# candy_v0001.net
KiCad netlist of a schematic drawn in EAGLE
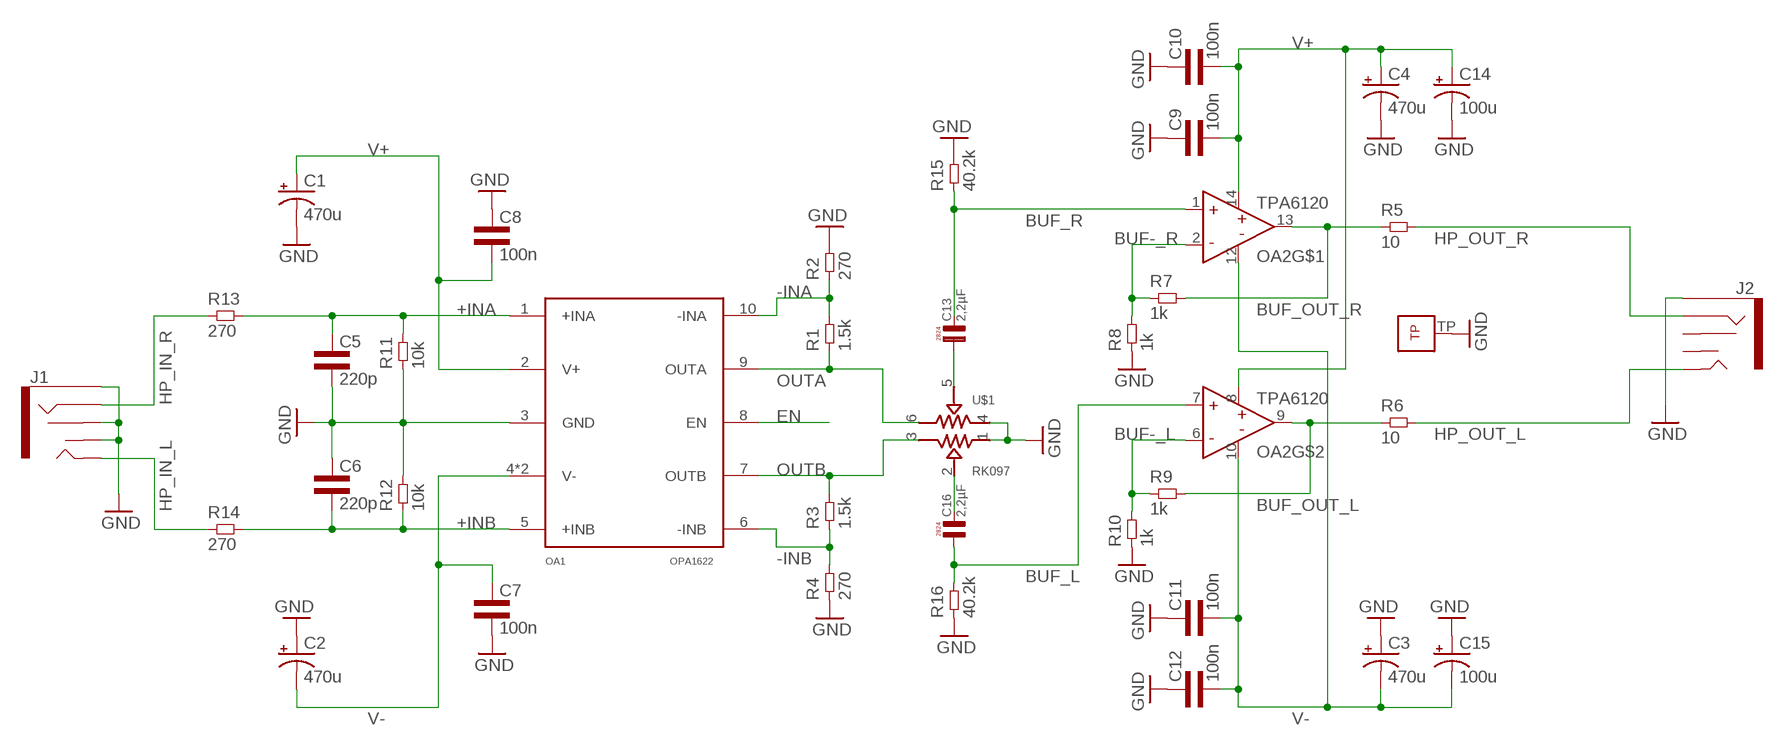
[diagram p0: schematic, sheet 1]

(export (version "E")
  (design (tool "Eeschema 10.0.6"))
  (components
    (comp (ref "C1")
      (value "470u")
      (footprint "eagle-import:PANASONIC_F")
      (libsource (lib "eagle-import") (part "CPOL-USF"))
    )
    (comp (ref "C2")
      (value "470u")
      (footprint "eagle-import:PANASONIC_F")
      (libsource (lib "eagle-import") (part "CPOL-USF"))
    )
    (comp (ref "C3")
      (value "470u")
      (footprint "eagle-import:PANASONIC_F")
      (libsource (lib "eagle-import") (part "CPOL-USF"))
    )
    (comp (ref "C4")
      (value "470u")
      (footprint "eagle-import:PANASONIC_F")
      (libsource (lib "eagle-import") (part "CPOL-USF"))
    )
    (comp (ref "C5")
      (value "220p")
      (footprint "eagle-import:0805L3")
      (libsource (lib "eagle-import") (part "CAP0805L3"))
    )
    (comp (ref "C6")
      (value "220p")
      (footprint "eagle-import:0805L3")
      (libsource (lib "eagle-import") (part "CAP0805L3"))
    )
    (comp (ref "C7")
      (value "100n")
      (footprint "eagle-import:0603L3")
      (libsource (lib "eagle-import") (part "CAP0603L3"))
    )
    (comp (ref "C8")
      (value "100n")
      (footprint "eagle-import:0603L3")
      (libsource (lib "eagle-import") (part "CAP0603L3"))
    )
    (comp (ref "C9")
      (value "100n")
      (footprint "eagle-import:0603L3")
      (libsource (lib "eagle-import") (part "CAP0603L3"))
    )
    (comp (ref "C10")
      (value "100n")
      (footprint "eagle-import:0603L3")
      (libsource (lib "eagle-import") (part "CAP0603L3"))
    )
    (comp (ref "C11")
      (value "100n")
      (footprint "eagle-import:0603L3")
      (libsource (lib "eagle-import") (part "CAP0603L3"))
    )
    (comp (ref "C12")
      (value "100n")
      (footprint "eagle-import:0603L3")
      (libsource (lib "eagle-import") (part "CAP0603L3"))
    )
    (comp (ref "C13")
      (value "2,2µF")
      (footprint "eagle-import:L7,2")
      (libsource (lib "eagle-import") (part "2,2µF"))
    )
    (comp (ref "C14")
      (value "100u")
      (footprint "eagle-import:PANASONIC_D")
      (libsource (lib "eagle-import") (part "CPOL-USD"))
    )
    (comp (ref "C15")
      (value "100u")
      (footprint "eagle-import:PANASONIC_D")
      (libsource (lib "eagle-import") (part "CPOL-USD"))
    )
    (comp (ref "C16")
      (value "2,2µF")
      (footprint "eagle-import:L7,2")
      (libsource (lib "eagle-import") (part "2,2µF"))
    )
    (comp (ref "J1")
      (value "AUDIO-JACK2SMD")
      (footprint "eagle-import:AUDIO-JACK-3.5MM-SMD")
      (libsource (lib "eagle-import") (part "AUDIO-JACK2SMD"))
    )
    (comp (ref "J2")
      (value "AUDIO-JACK2SMD")
      (footprint "eagle-import:AUDIO-JACK-3.5MM-SMD")
      (libsource (lib "eagle-import") (part "AUDIO-JACK2SMD"))
    )
    (comp (ref "OA1")
      (value "OPA1622")
      (footprint "eagle-import:S-PVSON-N10")
      (libsource (lib "eagle-import") (part "OPA1622"))
    )
    (comp (ref "OA2")
      (value "TPA6120QFN")
      (footprint "eagle-import:S-PVQFN-N14")
      (libsource (lib "eagle-import") (part "TPA6120QFN"))
    )
    (comp (ref "R1")
      (value "1.5k")
      (footprint "eagle-import:0603L3")
      (libsource (lib "eagle-import") (part "RES0603L3"))
    )
    (comp (ref "R2")
      (value "270")
      (footprint "eagle-import:0603L3")
      (libsource (lib "eagle-import") (part "RES0603L3"))
    )
    (comp (ref "R3")
      (value "1.5k")
      (footprint "eagle-import:0603L3")
      (libsource (lib "eagle-import") (part "RES0603L3"))
    )
    (comp (ref "R4")
      (value "270")
      (footprint "eagle-import:0603L3")
      (libsource (lib "eagle-import") (part "RES0603L3"))
    )
    (comp (ref "R5")
      (value "10")
      (footprint "eagle-import:1206L3")
      (libsource (lib "eagle-import") (part "RES1206L3"))
    )
    (comp (ref "R6")
      (value "10")
      (footprint "eagle-import:1206L3")
      (libsource (lib "eagle-import") (part "RES1206L3"))
    )
    (comp (ref "R7")
      (value "1k")
      (footprint "eagle-import:0603L3")
      (libsource (lib "eagle-import") (part "RES0603L3"))
    )
    (comp (ref "R8")
      (value "1k")
      (footprint "eagle-import:0603L3")
      (libsource (lib "eagle-import") (part "RES0603L3"))
    )
    (comp (ref "R9")
      (value "1k")
      (footprint "eagle-import:0603L3")
      (libsource (lib "eagle-import") (part "RES0603L3"))
    )
    (comp (ref "R10")
      (value "1k")
      (footprint "eagle-import:0603L3")
      (libsource (lib "eagle-import") (part "RES0603L3"))
    )
    (comp (ref "R11")
      (value "10k")
      (footprint "eagle-import:0603L3")
      (libsource (lib "eagle-import") (part "RES0603L3"))
    )
    (comp (ref "R12")
      (value "10k")
      (footprint "eagle-import:0603L3")
      (libsource (lib "eagle-import") (part "RES0603L3"))
    )
    (comp (ref "R13")
      (value "270")
      (footprint "eagle-import:0603L3")
      (libsource (lib "eagle-import") (part "RES0603L3"))
    )
    (comp (ref "R14")
      (value "270")
      (footprint "eagle-import:0603L3")
      (libsource (lib "eagle-import") (part "RES0603L3"))
    )
    (comp (ref "R15")
      (value "40.2k")
      (footprint "eagle-import:0603L3")
      (libsource (lib "eagle-import") (part "RES0603L3"))
    )
    (comp (ref "R16")
      (value "40.2k")
      (footprint "eagle-import:0603L3")
      (libsource (lib "eagle-import") (part "RES0603L3"))
    )
    (comp (ref "U$1")
      (value "RK097")
      (footprint "eagle-import:RK097")
      (libsource (lib "eagle-import") (part "RK097"))
    )
  )
  (nets
    (net (code "1") (name "/+INA") (class "Default")
      (node (ref "C5") (pin "1") (pinfunction "1_1") (pintype "bidirectional"))
      (node (ref "OA1") (pin "1") (pinfunction "+INA_1") (pintype "bidirectional"))
      (node (ref "R11") (pin "P$2") (pinfunction "2_P$2") (pintype "bidirectional"))
      (node (ref "R13") (pin "P$2") (pinfunction "2_P$2") (pintype "bidirectional"))
    )
    (net (code "2") (name "/+INB") (class "Default")
      (node (ref "C6") (pin "2") (pinfunction "2_2") (pintype "bidirectional"))
      (node (ref "OA1") (pin "5") (pinfunction "+INB_5") (pintype "bidirectional"))
      (node (ref "R12") (pin "P$1") (pinfunction "1_P$1") (pintype "bidirectional"))
      (node (ref "R14") (pin "P$2") (pinfunction "2_P$2") (pintype "bidirectional"))
    )
    (net (code "3") (name "/-INA") (class "Default")
      (node (ref "OA1") (pin "10") (pinfunction "-INA_10") (pintype "bidirectional"))
      (node (ref "R1") (pin "P$2") (pinfunction "2_P$2") (pintype "bidirectional"))
      (node (ref "R2") (pin "P$1") (pinfunction "1_P$1") (pintype "bidirectional"))
    )
    (net (code "4") (name "/-INB") (class "Default")
      (node (ref "OA1") (pin "6") (pinfunction "-INB_6") (pintype "bidirectional"))
      (node (ref "R3") (pin "P$1") (pinfunction "1_P$1") (pintype "bidirectional"))
      (node (ref "R4") (pin "P$2") (pinfunction "2_P$2") (pintype "bidirectional"))
    )
    (net (code "5") (name "/BUF-_L") (class "Default")
      (node (ref "OA2") (pin "6") (pinfunction "IN-_6") (pintype "bidirectional"))
      (node (ref "R10") (pin "P$2") (pinfunction "2_P$2") (pintype "bidirectional"))
      (node (ref "R9") (pin "P$1") (pinfunction "1_P$1") (pintype "bidirectional"))
    )
    (net (code "6") (name "/BUF-_R") (class "Default")
      (node (ref "OA2") (pin "2") (pinfunction "IN-_2") (pintype "bidirectional"))
      (node (ref "R7") (pin "P$1") (pinfunction "1_P$1") (pintype "bidirectional"))
      (node (ref "R8") (pin "P$2") (pinfunction "2_P$2") (pintype "bidirectional"))
    )
    (net (code "7") (name "/BUF_L") (class "Default")
      (node (ref "C16") (pin "P$1") (pinfunction "1_P$1") (pintype "passive"))
      (node (ref "OA2") (pin "7") (pinfunction "IN+_7") (pintype "bidirectional"))
      (node (ref "R16") (pin "P$2") (pinfunction "2_P$2") (pintype "bidirectional"))
    )
    (net (code "8") (name "/BUF_OUT_L") (class "Default")
      (node (ref "OA2") (pin "9") (pinfunction "OUT_9") (pintype "bidirectional"))
      (node (ref "R6") (pin "1") (pinfunction "1_1") (pintype "bidirectional"))
      (node (ref "R9") (pin "P$2") (pinfunction "2_P$2") (pintype "bidirectional"))
    )
    (net (code "9") (name "/BUF_OUT_R") (class "Default")
      (node (ref "OA2") (pin "13") (pinfunction "OUT_13") (pintype "bidirectional"))
      (node (ref "R5") (pin "1") (pinfunction "1_1") (pintype "bidirectional"))
      (node (ref "R7") (pin "P$2") (pinfunction "2_P$2") (pintype "bidirectional"))
    )
    (net (code "10") (name "/BUF_R") (class "Default")
      (node (ref "C13") (pin "P$2") (pinfunction "2_P$2") (pintype "passive"))
      (node (ref "OA2") (pin "1") (pinfunction "IN+_1") (pintype "bidirectional"))
      (node (ref "R15") (pin "P$1") (pinfunction "1_P$1") (pintype "bidirectional"))
    )
    (net (code "11") (name "/EN") (class "Default")
      (node (ref "OA1") (pin "8") (pinfunction "EN_8") (pintype "bidirectional"))
    )
    (net (code "12") (name "/HP_IN_L") (class "Default")
      (node (ref "J1") (pin "TIP") (pinfunction "TIP_TIP") (pintype "bidirectional"))
      (node (ref "R14") (pin "P$1") (pinfunction "1_P$1") (pintype "bidirectional"))
    )
    (net (code "13") (name "/HP_IN_R") (class "Default")
      (node (ref "J1") (pin "RING") (pinfunction "RING_RING") (pintype "bidirectional"))
      (node (ref "R13") (pin "P$1") (pinfunction "1_P$1") (pintype "bidirectional"))
    )
    (net (code "14") (name "/HP_OUT_L") (class "Default")
      (node (ref "J2") (pin "TIP") (pinfunction "TIP_TIP") (pintype "bidirectional"))
      (node (ref "R6") (pin "2") (pinfunction "2_2") (pintype "bidirectional"))
    )
    (net (code "15") (name "/HP_OUT_R") (class "Default")
      (node (ref "J2") (pin "RING") (pinfunction "RING_RING") (pintype "bidirectional"))
      (node (ref "R5") (pin "2") (pinfunction "2_2") (pintype "bidirectional"))
    )
    (net (code "16") (name "/OUTA") (class "Default")
      (node (ref "OA1") (pin "9") (pinfunction "OUTA_9") (pintype "bidirectional"))
      (node (ref "R1") (pin "P$1") (pinfunction "1_P$1") (pintype "bidirectional"))
      (node (ref "U$1") (pin "6") (pinfunction "6_6") (pintype "bidirectional"))
    )
    (net (code "17") (name "/OUTB") (class "Default")
      (node (ref "OA1") (pin "7") (pinfunction "OUTB_7") (pintype "bidirectional"))
      (node (ref "R3") (pin "P$2") (pinfunction "2_P$2") (pintype "bidirectional"))
      (node (ref "U$1") (pin "3") (pinfunction "3_3") (pintype "bidirectional"))
    )
    (net (code "18") (name "/V+") (class "Default")
      (node (ref "C1") (pin "+") (pinfunction "+_+") (pintype "passive"))
      (node (ref "C10") (pin "P$2") (pinfunction "2_P$2") (pintype "bidirectional"))
      (node (ref "C14") (pin "+") (pinfunction "+_+") (pintype "passive"))
      (node (ref "C4") (pin "+") (pinfunction "+_+") (pintype "passive"))
      (node (ref "C8") (pin "P$2") (pinfunction "2_P$2") (pintype "bidirectional"))
      (node (ref "C9") (pin "P$2") (pinfunction "2_P$2") (pintype "bidirectional"))
      (node (ref "OA1") (pin "2") (pinfunction "V+_2") (pintype "bidirectional"))
      (node (ref "OA2") (pin "14") (pinfunction "V+_14") (pintype "bidirectional"))
      (node (ref "OA2") (pin "8") (pinfunction "V+_8") (pintype "bidirectional"))
    )
    (net (code "19") (name "/V-") (class "Default")
      (node (ref "C11") (pin "P$2") (pinfunction "2_P$2") (pintype "bidirectional"))
      (node (ref "C12") (pin "P$2") (pinfunction "2_P$2") (pintype "bidirectional"))
      (node (ref "C15") (pin "-") (pinfunction "-_-") (pintype "passive"))
      (node (ref "C2") (pin "-") (pinfunction "-_-") (pintype "passive"))
      (node (ref "C3") (pin "-") (pinfunction "-_-") (pintype "passive"))
      (node (ref "C7") (pin "P$1") (pinfunction "1_P$1") (pintype "bidirectional"))
      (node (ref "OA1") (pin "4") (pinfunction "V-_4") (pintype "bidirectional"))
      (node (ref "OA1") (pin "TP") (pinfunction "V-_TP") (pintype "bidirectional"))
      (node (ref "OA2") (pin "10") (pinfunction "V-_10") (pintype "bidirectional"))
      (node (ref "OA2") (pin "12") (pinfunction "V-_12") (pintype "bidirectional"))
    )
    (net (code "20") (name "GND") (class "Default")
      (node (ref "C1") (pin "-") (pinfunction "-_-") (pintype "passive"))
      (node (ref "C10") (pin "P$1") (pinfunction "1_P$1") (pintype "bidirectional"))
      (node (ref "C11") (pin "P$1") (pinfunction "1_P$1") (pintype "bidirectional"))
      (node (ref "C12") (pin "P$1") (pinfunction "1_P$1") (pintype "bidirectional"))
      (node (ref "C14") (pin "-") (pinfunction "-_-") (pintype "passive"))
      (node (ref "C15") (pin "+") (pinfunction "+_+") (pintype "passive"))
      (node (ref "C2") (pin "+") (pinfunction "+_+") (pintype "passive"))
      (node (ref "C3") (pin "+") (pinfunction "+_+") (pintype "passive"))
      (node (ref "C4") (pin "-") (pinfunction "-_-") (pintype "passive"))
      (node (ref "C5") (pin "2") (pinfunction "2_2") (pintype "bidirectional"))
      (node (ref "C6") (pin "1") (pinfunction "1_1") (pintype "bidirectional"))
      (node (ref "C7") (pin "P$2") (pinfunction "2_P$2") (pintype "bidirectional"))
      (node (ref "C8") (pin "P$1") (pinfunction "1_P$1") (pintype "bidirectional"))
      (node (ref "C9") (pin "P$1") (pinfunction "1_P$1") (pintype "bidirectional"))
      (node (ref "J1") (pin "RSH") (pinfunction "RSH_RSH") (pintype "bidirectional"))
      (node (ref "J1") (pin "SLEEVE") (pinfunction "SLEEVE_SLEEVE") (pintype "bidirectional"))
      (node (ref "J1") (pin "TSH") (pinfunction "TSH_TSH") (pintype "bidirectional"))
      (node (ref "J2") (pin "SLEEVE") (pinfunction "SLEEVE_SLEEVE") (pintype "bidirectional"))
      (node (ref "OA1") (pin "3") (pinfunction "GND_3") (pintype "bidirectional"))
      (node (ref "OA2") (pin "TP") (pinfunction "TP_TP") (pintype "bidirectional"))
      (node (ref "R10") (pin "P$1") (pinfunction "1_P$1") (pintype "bidirectional"))
      (node (ref "R11") (pin "P$1") (pinfunction "1_P$1") (pintype "bidirectional"))
      (node (ref "R12") (pin "P$2") (pinfunction "2_P$2") (pintype "bidirectional"))
      (node (ref "R15") (pin "P$2") (pinfunction "2_P$2") (pintype "bidirectional"))
      (node (ref "R16") (pin "P$1") (pinfunction "1_P$1") (pintype "bidirectional"))
      (node (ref "R2") (pin "P$2") (pinfunction "2_P$2") (pintype "bidirectional"))
      (node (ref "R4") (pin "P$1") (pinfunction "1_P$1") (pintype "bidirectional"))
      (node (ref "R8") (pin "P$1") (pinfunction "1_P$1") (pintype "bidirectional"))
      (node (ref "U$1") (pin "1") (pinfunction "1_1") (pintype "bidirectional"))
      (node (ref "U$1") (pin "4") (pinfunction "4_4") (pintype "bidirectional"))
    )
    (net (code "21") (name "Net-(C13-1)") (class "Default")
      (node (ref "C13") (pin "P$1") (pinfunction "1_P$1") (pintype "passive"))
      (node (ref "U$1") (pin "5") (pinfunction "5_5") (pintype "bidirectional"))
    )
    (net (code "22") (name "Net-(C16-2)") (class "Default")
      (node (ref "C16") (pin "P$2") (pinfunction "2_P$2") (pintype "passive"))
      (node (ref "U$1") (pin "2") (pinfunction "2_2") (pintype "bidirectional"))
    )
    (net (code "23") (name "unconnected-(J2-PadRSH)") (class "Default")
      (node (ref "J2") (pin "RSH") (pinfunction "RSH_RSH") (pintype "bidirectional"))
    )
    (net (code "24") (name "unconnected-(J2-PadTSH)") (class "Default")
      (node (ref "J2") (pin "TSH") (pinfunction "TSH_TSH") (pintype "bidirectional"))
    )
  )
)
